# S7G2_footprint_with_caps_v1p0.net
KiCad netlist of a schematic drawn in EAGLE
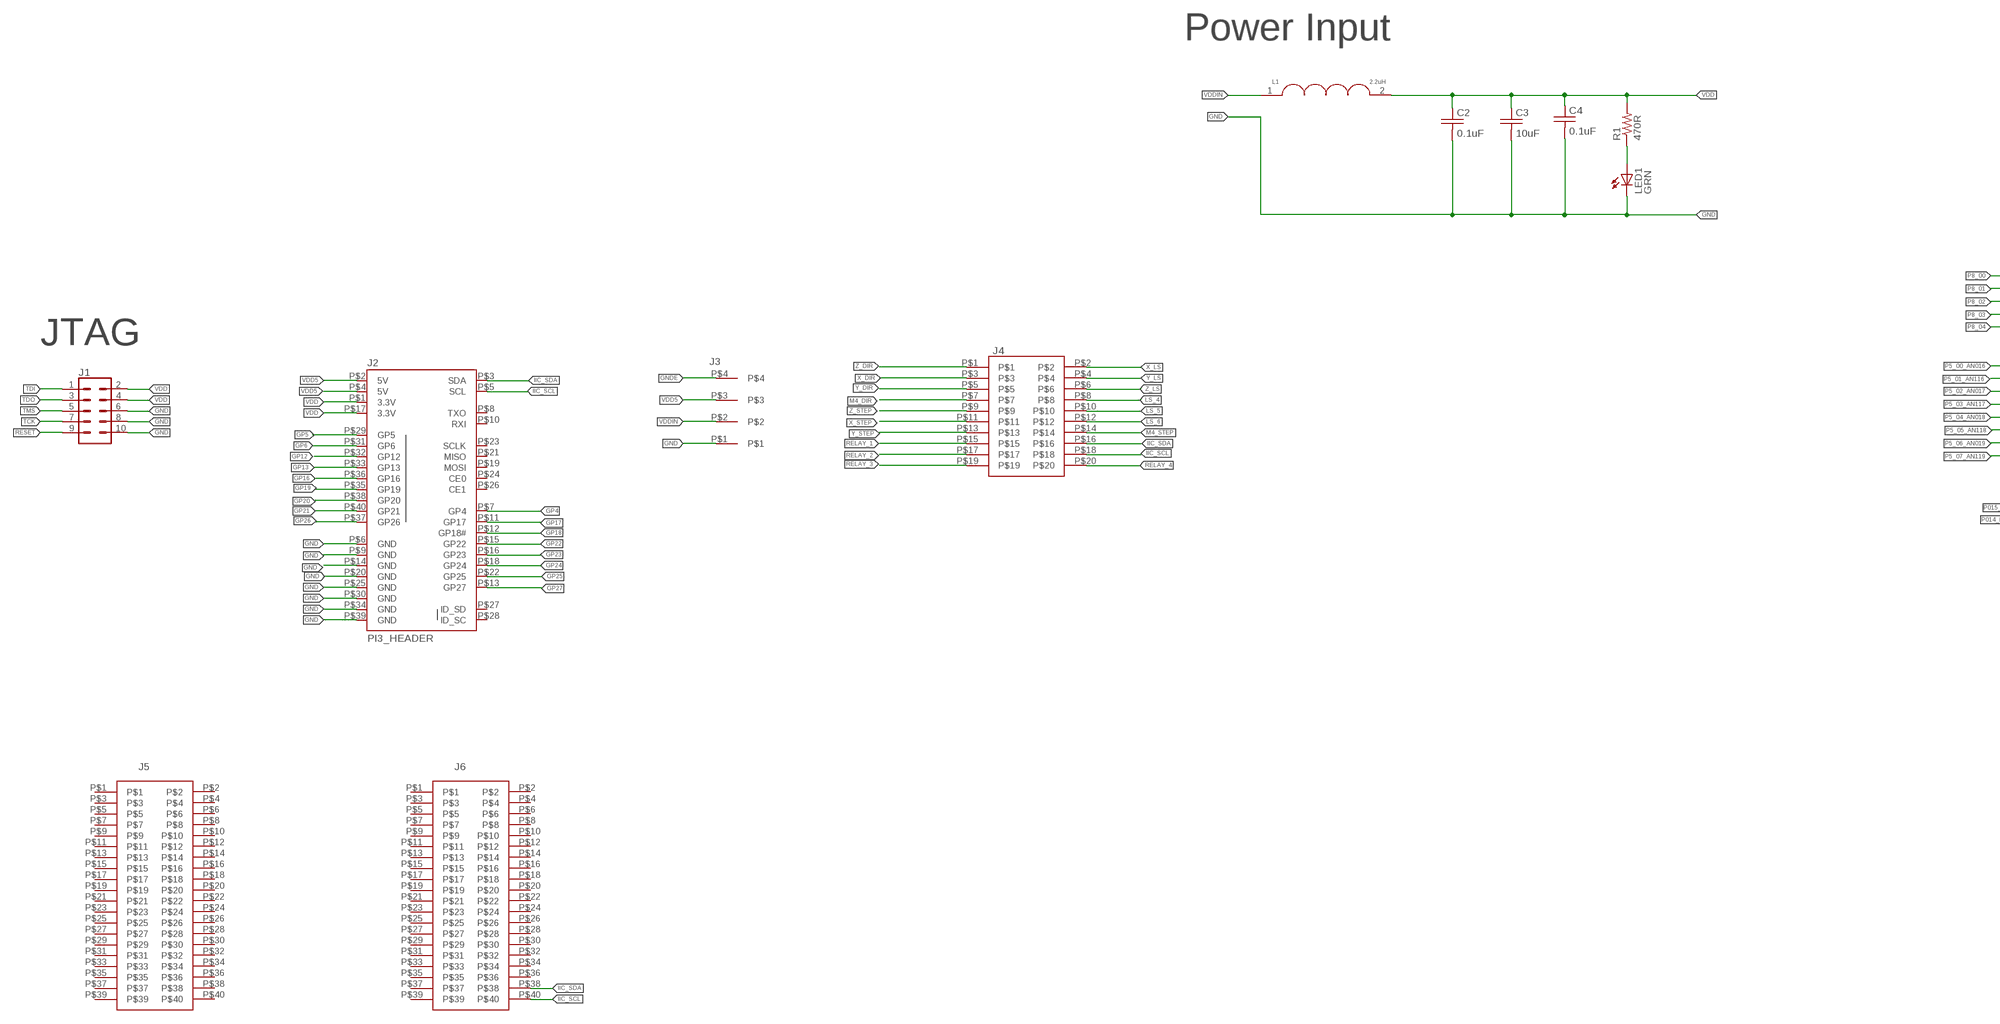
[diagram p0: schematic, sheet 1, part 1 of 3]
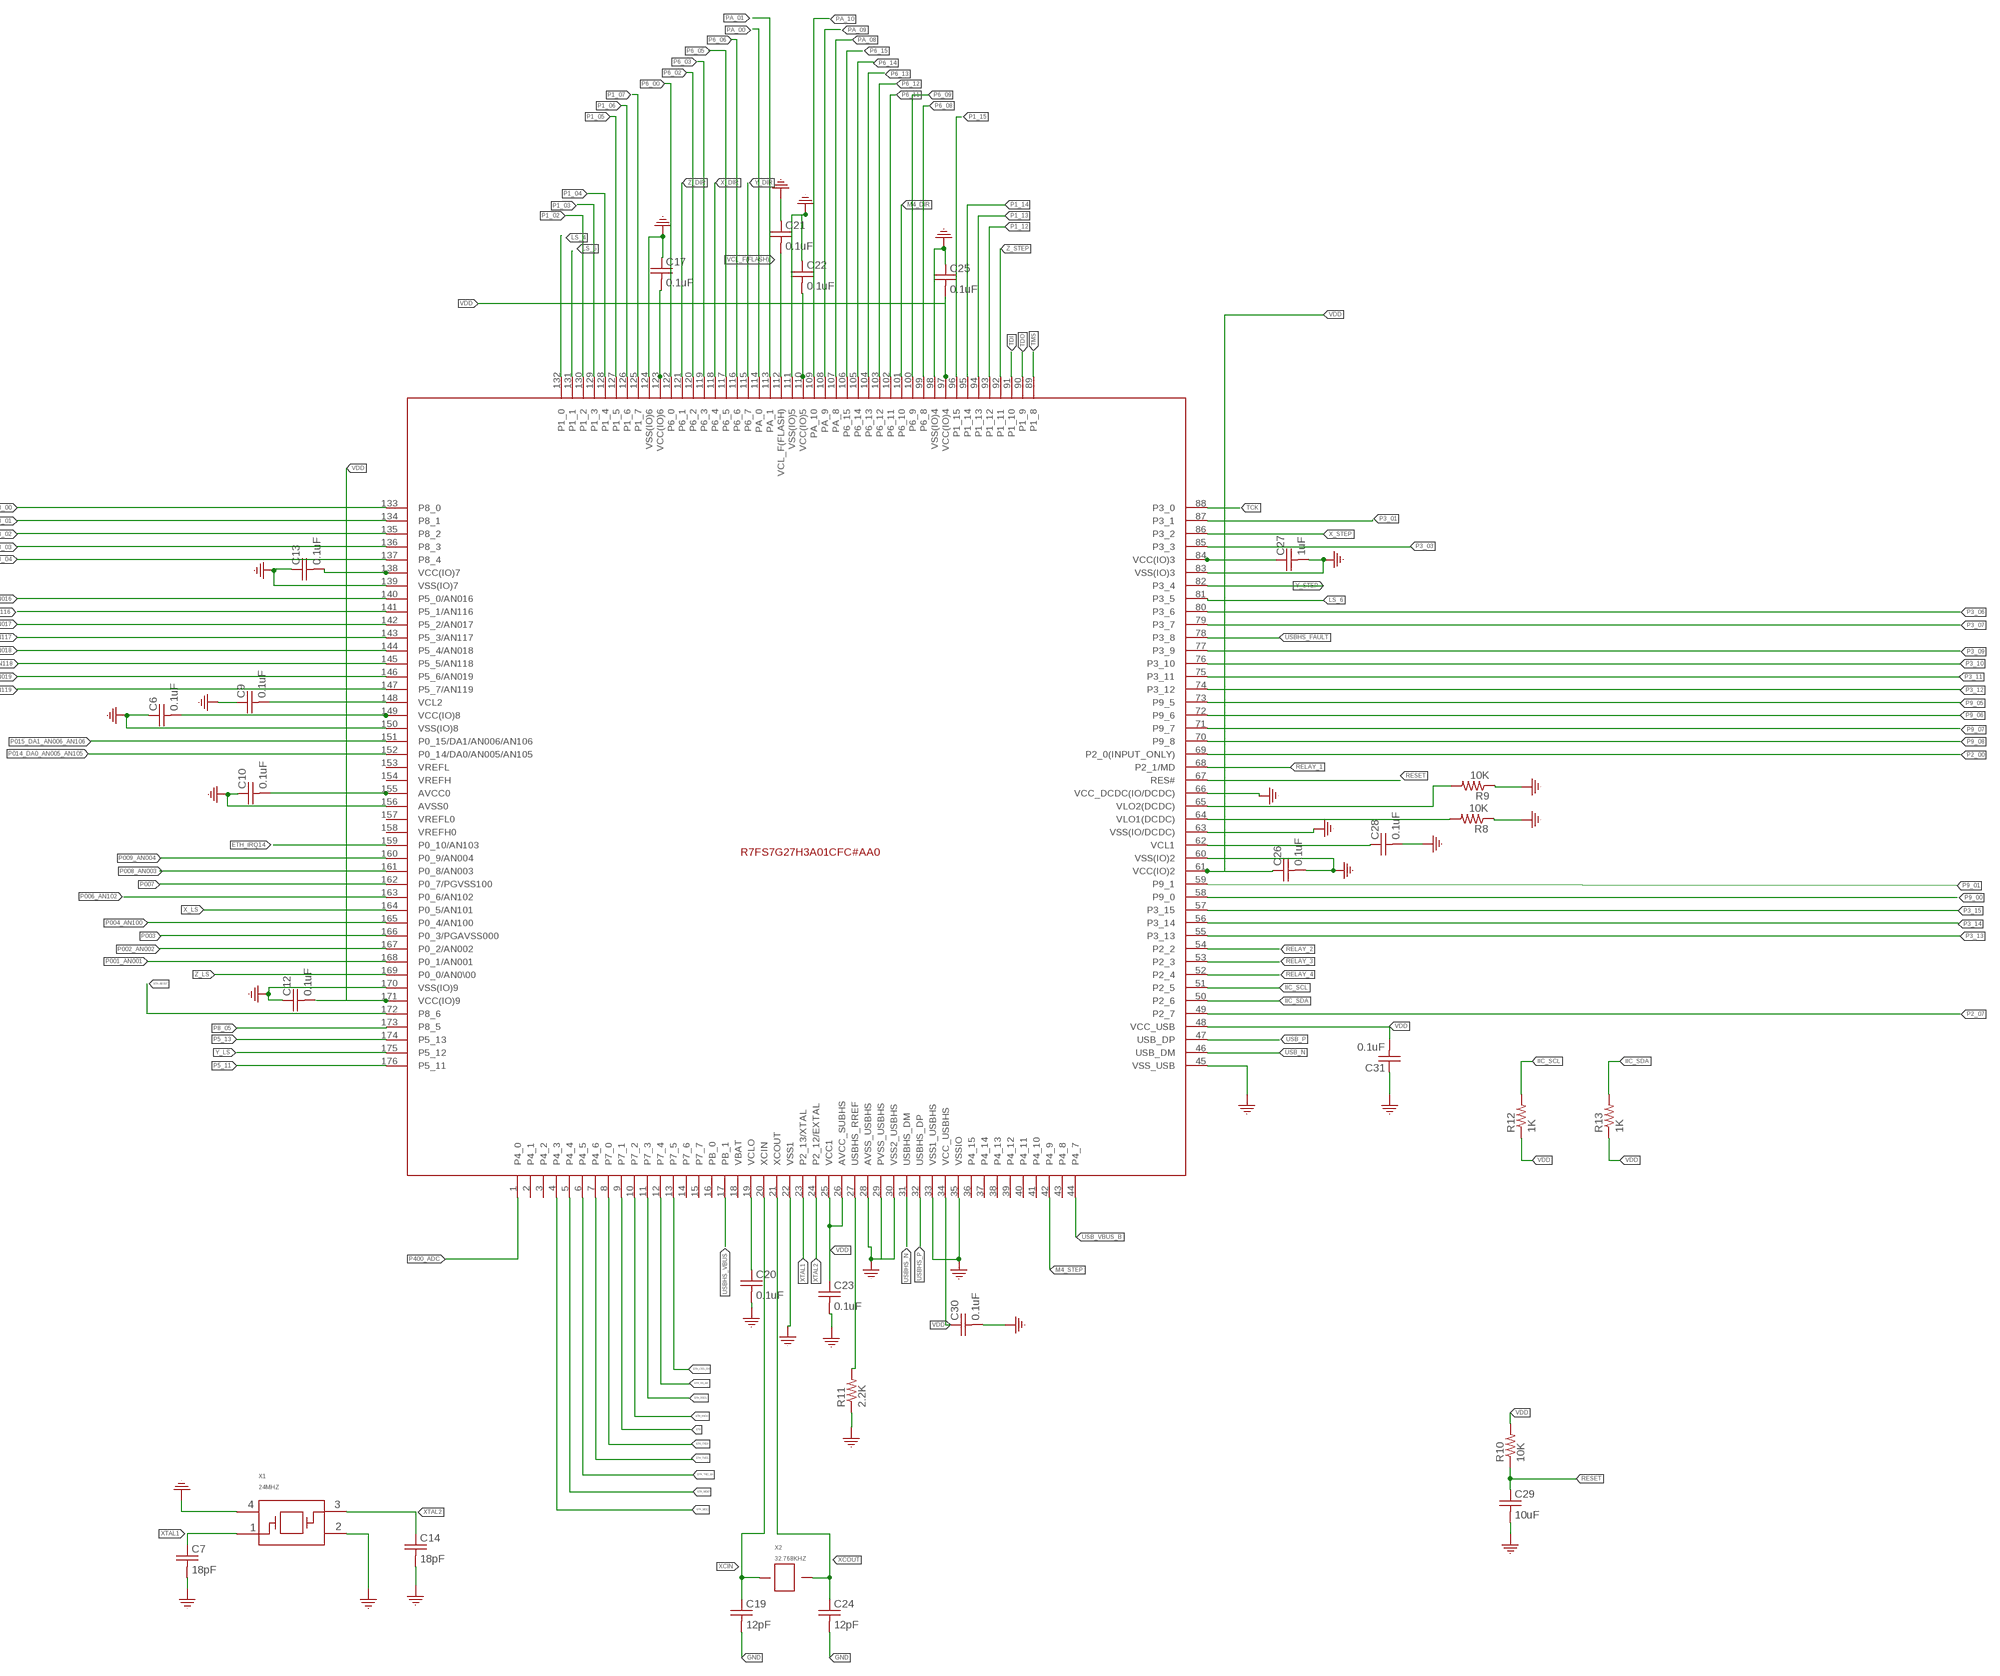
[diagram p1: schematic, sheet 1, part 2 of 3]
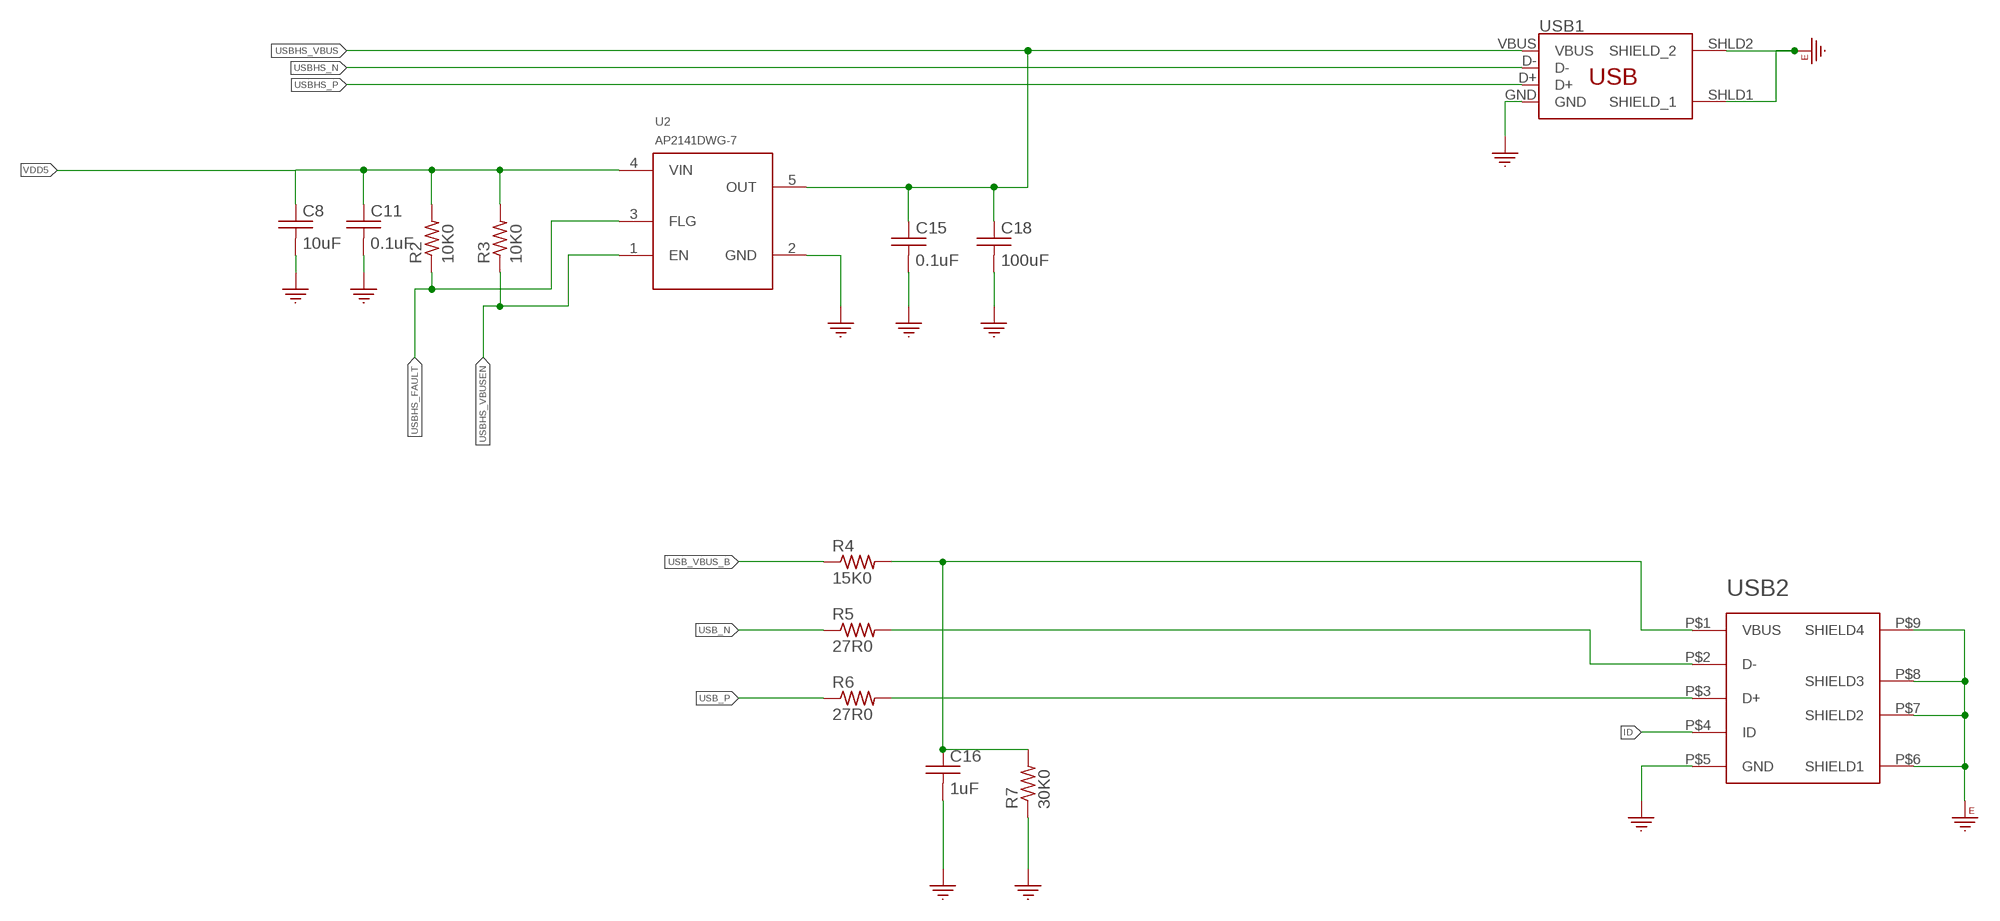
[diagram p2: schematic, sheet 1, part 3 of 3]

(export (version "E")
  (design (tool "Eeschema 10.0.6"))
  (components
    (comp (ref "C2")
      (value "0.1uF")
      (footprint "eagle-import:0402")
      (libsource (lib "eagle-import") (part "C_0402"))
    )
    (comp (ref "C3")
      (value "10uF")
      (footprint "eagle-import:0402")
      (libsource (lib "eagle-import") (part "C_0402"))
    )
    (comp (ref "C4")
      (value "0.1uF")
      (footprint "eagle-import:0402")
      (libsource (lib "eagle-import") (part "C_0402"))
    )
    (comp (ref "C6")
      (value "0.1uF")
      (footprint "eagle-import:0402")
      (libsource (lib "eagle-import") (part "C_0402"))
    )
    (comp (ref "C7")
      (value "18pF")
      (footprint "eagle-import:0402")
      (libsource (lib "eagle-import") (part "C_0402"))
    )
    (comp (ref "C8")
      (value "10uF")
      (footprint "eagle-import:0402")
      (libsource (lib "eagle-import") (part "C_0402"))
    )
    (comp (ref "C9")
      (value "0.1uF")
      (footprint "eagle-import:0402")
      (libsource (lib "eagle-import") (part "C_0402"))
    )
    (comp (ref "C10")
      (value "0.1uF")
      (footprint "eagle-import:0402")
      (libsource (lib "eagle-import") (part "C_0402"))
    )
    (comp (ref "C11")
      (value "0.1uF")
      (footprint "eagle-import:0402")
      (libsource (lib "eagle-import") (part "C_0402"))
    )
    (comp (ref "C12")
      (value "0.1uF")
      (footprint "eagle-import:0402")
      (libsource (lib "eagle-import") (part "C_0402"))
    )
    (comp (ref "C13")
      (value "0.1uF")
      (footprint "eagle-import:0402")
      (libsource (lib "eagle-import") (part "C_0402"))
    )
    (comp (ref "C14")
      (value "18pF")
      (footprint "eagle-import:0402")
      (libsource (lib "eagle-import") (part "C_0402"))
    )
    (comp (ref "C15")
      (value "0.1uF")
      (footprint "eagle-import:0402")
      (libsource (lib "eagle-import") (part "C_0402"))
    )
    (comp (ref "C16")
      (value "1uF")
      (footprint "eagle-import:0402")
      (libsource (lib "eagle-import") (part "C_0402"))
    )
    (comp (ref "C17")
      (value "0.1uF")
      (footprint "eagle-import:0402")
      (libsource (lib "eagle-import") (part "C_0402"))
    )
    (comp (ref "C18")
      (value "100uF")
      (footprint "eagle-import:C1210")
      (libsource (lib "eagle-import") (part "C_1210"))
    )
    (comp (ref "C19")
      (value "12pF")
      (footprint "eagle-import:0402")
      (libsource (lib "eagle-import") (part "C_0402"))
    )
    (comp (ref "C20")
      (value "0.1uF")
      (footprint "eagle-import:0402")
      (libsource (lib "eagle-import") (part "C_0402"))
    )
    (comp (ref "C21")
      (value "0.1uF")
      (footprint "eagle-import:0402")
      (libsource (lib "eagle-import") (part "C_0402"))
    )
    (comp (ref "C22")
      (value "0.1uF")
      (footprint "eagle-import:0402")
      (libsource (lib "eagle-import") (part "C_0402"))
    )
    (comp (ref "C23")
      (value "0.1uF")
      (footprint "eagle-import:0402")
      (libsource (lib "eagle-import") (part "C_0402"))
    )
    (comp (ref "C24")
      (value "12pF")
      (footprint "eagle-import:0402")
      (libsource (lib "eagle-import") (part "C_0402"))
    )
    (comp (ref "C25")
      (value "0.1uF")
      (footprint "eagle-import:0402")
      (libsource (lib "eagle-import") (part "C_0402"))
    )
    (comp (ref "C26")
      (value "0.1uF")
      (footprint "eagle-import:0402")
      (libsource (lib "eagle-import") (part "C_0402"))
    )
    (comp (ref "C27")
      (value "1uF")
      (footprint "eagle-import:0402")
      (libsource (lib "eagle-import") (part "C_0402"))
    )
    (comp (ref "C28")
      (value "0.1uF")
      (footprint "eagle-import:0402")
      (libsource (lib "eagle-import") (part "C_0402"))
    )
    (comp (ref "C29")
      (value "10uF")
      (footprint "eagle-import:0402")
      (libsource (lib "eagle-import") (part "C_0402"))
    )
    (comp (ref "C30")
      (value "0.1uF")
      (footprint "eagle-import:0402")
      (libsource (lib "eagle-import") (part "C_0402"))
    )
    (comp (ref "C31")
      (value "0.1uF")
      (footprint "eagle-import:0402")
      (libsource (lib "eagle-import") (part "C_0402"))
    )
    (comp (ref "J1")
      (value "CONN_05X2PTH")
      (footprint "eagle-import:2X5")
      (libsource (lib "eagle-import") (part "CONN_05X2PTH"))
    )
    (comp (ref "J2")
      (value "PI3_HEADER")
      (footprint "eagle-import:HEADER_2_X_20_.1_INCH")
      (libsource (lib "eagle-import") (part "PI3_HEADER"))
    )
    (comp (ref "J3")
      (value "3.81MM_1_X_4_RT_ANGLE_PLUG_HEADER")
      (footprint "eagle-import:1X4_3.81MM_PITCH")
      (libsource (lib "eagle-import") (part "3.81MM_1_X_4_RT_ANGLE_PLUG_HEADER"))
    )
    (comp (ref "J4")
      (value "2_X_10_HEADER_GENERIC")
      (footprint "eagle-import:2_X_10_.1_INCH")
      (libsource (lib "eagle-import") (part "2_X_10_HEADER_GENERIC"))
    )
    (comp (ref "J5")
      (value "HEADER_2_X_20_GENERIC")
      (footprint "eagle-import:HEADER_2_X_20_.1_INCH")
      (libsource (lib "eagle-import") (part "HEADER_2_X_20_GENERIC"))
    )
    (comp (ref "J6")
      (value "HEADER_2_X_20_GENERIC")
      (footprint "eagle-import:HEADER_2_X_20_.1_INCH")
      (libsource (lib "eagle-import") (part "HEADER_2_X_20_GENERIC"))
    )
    (comp (ref "L1")
      (value "2.2uH")
      (footprint "eagle-import:1008_(2520_METRIC)")
      (libsource (lib "eagle-import") (part "INDUCTOR_1008_2.2_MH_1.3A"))
    )
    (comp (ref "LED1")
      (value "LED_0805_GREEN")
      (footprint "eagle-import:LED_0805_GREEN")
      (libsource (lib "eagle-import") (part "LED_0805_GREEN"))
    )
    (comp (ref "R1")
      (value "470R")
      (footprint "eagle-import:0402")
      (libsource (lib "eagle-import") (part "R_0402"))
    )
    (comp (ref "R2")
      (value "10K0")
      (footprint "eagle-import:0402")
      (libsource (lib "eagle-import") (part "R_0402"))
    )
    (comp (ref "R3")
      (value "10K0")
      (footprint "eagle-import:0402")
      (libsource (lib "eagle-import") (part "R_0402"))
    )
    (comp (ref "R4")
      (value "15K0")
      (footprint "eagle-import:0402")
      (libsource (lib "eagle-import") (part "R_0402"))
    )
    (comp (ref "R5")
      (value "27R0")
      (footprint "eagle-import:0402")
      (libsource (lib "eagle-import") (part "R_0402"))
    )
    (comp (ref "R6")
      (value "27R0")
      (footprint "eagle-import:0402")
      (libsource (lib "eagle-import") (part "R_0402"))
    )
    (comp (ref "R7")
      (value "30K0")
      (footprint "eagle-import:0402")
      (libsource (lib "eagle-import") (part "R_0402"))
    )
    (comp (ref "R8")
      (value "10K")
      (footprint "eagle-import:0402")
      (libsource (lib "eagle-import") (part "R_0402"))
    )
    (comp (ref "R9")
      (value "10K")
      (footprint "eagle-import:0402")
      (libsource (lib "eagle-import") (part "R_0402"))
    )
    (comp (ref "R10")
      (value "10K")
      (footprint "eagle-import:0402")
      (libsource (lib "eagle-import") (part "R_0402"))
    )
    (comp (ref "R11")
      (value "2.2K")
      (footprint "eagle-import:0402")
      (libsource (lib "eagle-import") (part "R_0402"))
    )
    (comp (ref "R12")
      (value "1K")
      (footprint "eagle-import:0402")
      (libsource (lib "eagle-import") (part "R_0402"))
    )
    (comp (ref "R13")
      (value "1K")
      (footprint "eagle-import:0402")
      (libsource (lib "eagle-import") (part "R_0402"))
    )
    (comp (ref "U2")
      (value "AP2141DWG-5")
      (footprint "eagle-import:SOT-23-5")
      (libsource (lib "eagle-import") (part "AP2141DWG-5"))
    )
    (comp (ref "U5")
      (value "S7G2_X_176")
      (footprint "eagle-import:LQFP176_24X24")
      (libsource (lib "eagle-import") (part "S7G2_X_176"))
    )
    (comp (ref "USB1")
      (value "USB_A")
      (footprint "eagle-import:USB_A_SMT")
      (libsource (lib "eagle-import") (part "USB_A"))
    )
    (comp (ref "USB2")
      (value "USB_MICRO-B")
      (footprint "eagle-import:USB_MICRO-B")
      (libsource (lib "eagle-import") (part "USB_MICRO-B"))
    )
    (comp (ref "X1")
      (value "24MHZ")
      (footprint "eagle-import:SMD_3225")
      (libsource (lib "eagle-import") (part "XTAL_24_MHZ"))
    )
    (comp (ref "X2")
      (value "32.768KHZ")
      (footprint "eagle-import:SMD_X_2_PADS")
      (libsource (lib "eagle-import") (part "XTAL_32.768KHZ"))
    )
  )
  (nets
    (net (code "1") (name "ETH") (class "Default")
      (node (ref "U5") (pin "9") (pinfunction "P7_1_9") (pintype "bidirectional"))
    )
    (net (code "2") (name "ETH_CRS_DV") (class "Default")
      (node (ref "U5") (pin "13") (pinfunction "P7_5_13") (pintype "bidirectional"))
    )
    (net (code "3") (name "ETH_IRQ14") (class "Default")
      (node (ref "U5") (pin "159") (pinfunction "P0_10/AN103_159") (pintype "bidirectional"))
    )
    (net (code "4") (name "ETH_MDC") (class "Default")
      (node (ref "U5") (pin "4") (pinfunction "P4_3_4") (pintype "bidirectional"))
    )
    (net (code "5") (name "ETH_MDIO") (class "Default")
      (node (ref "U5") (pin "5") (pinfunction "P4_4_5") (pintype "bidirectional"))
    )
    (net (code "6") (name "ETH_RESET") (class "Default")
      (node (ref "U5") (pin "172") (pinfunction "P8_6_172") (pintype "bidirectional"))
    )
    (net (code "7") (name "ETH_RXD0") (class "Default")
      (node (ref "U5") (pin "10") (pinfunction "P7_2_10") (pintype "bidirectional"))
    )
    (net (code "8") (name "ETH_RXD1") (class "Default")
      (node (ref "U5") (pin "11") (pinfunction "P7_3_11") (pintype "bidirectional"))
    )
    (net (code "9") (name "ETH_RX_ER") (class "Default")
      (node (ref "U5") (pin "12") (pinfunction "P7_4_12") (pintype "bidirectional"))
    )
    (net (code "10") (name "ETH_TXD0") (class "Default")
      (node (ref "U5") (pin "8") (pinfunction "P7_0_8") (pintype "bidirectional"))
    )
    (net (code "11") (name "ETH_TXD1") (class "Default")
      (node (ref "U5") (pin "7") (pinfunction "P4_6_7") (pintype "bidirectional"))
    )
    (net (code "12") (name "ETH_TXD_EN") (class "Default")
      (node (ref "U5") (pin "6") (pinfunction "P4_5_6") (pintype "bidirectional"))
    )
    (net (code "13") (name "GND") (class "Default")
      (node (ref "C10") (pin "P$1") (pinfunction "1_P$1") (pintype "passive"))
      (node (ref "C11") (pin "P$2") (pinfunction "2_P$2") (pintype "passive"))
      (node (ref "C12") (pin "P$1") (pinfunction "1_P$1") (pintype "passive"))
      (node (ref "C13") (pin "P$1") (pinfunction "1_P$1") (pintype "passive"))
      (node (ref "C14") (pin "P$2") (pinfunction "2_P$2") (pintype "passive"))
      (node (ref "C15") (pin "P$2") (pinfunction "2_P$2") (pintype "passive"))
      (node (ref "C16") (pin "P$2") (pinfunction "2_P$2") (pintype "passive"))
      (node (ref "C17") (pin "P$1") (pinfunction "1_P$1") (pintype "passive"))
      (node (ref "C18") (pin "2") (pinfunction "2_2") (pintype "passive"))
      (node (ref "C19") (pin "P$2") (pinfunction "2_P$2") (pintype "passive"))
      (node (ref "C2") (pin "P$2") (pinfunction "2_P$2") (pintype "passive"))
      (node (ref "C20") (pin "P$2") (pinfunction "2_P$2") (pintype "passive"))
      (node (ref "C21") (pin "P$1") (pinfunction "1_P$1") (pintype "passive"))
      (node (ref "C22") (pin "P$1") (pinfunction "1_P$1") (pintype "passive"))
      (node (ref "C23") (pin "P$2") (pinfunction "2_P$2") (pintype "passive"))
      (node (ref "C24") (pin "P$2") (pinfunction "2_P$2") (pintype "passive"))
      (node (ref "C25") (pin "P$1") (pinfunction "1_P$1") (pintype "passive"))
      (node (ref "C26") (pin "P$2") (pinfunction "2_P$2") (pintype "passive"))
      (node (ref "C27") (pin "P$2") (pinfunction "2_P$2") (pintype "passive"))
      (node (ref "C28") (pin "P$2") (pinfunction "2_P$2") (pintype "passive"))
      (node (ref "C29") (pin "P$2") (pinfunction "2_P$2") (pintype "passive"))
      (node (ref "C3") (pin "P$2") (pinfunction "2_P$2") (pintype "passive"))
      (node (ref "C30") (pin "P$2") (pinfunction "2_P$2") (pintype "passive"))
      (node (ref "C31") (pin "P$1") (pinfunction "1_P$1") (pintype "passive"))
      (node (ref "C4") (pin "P$2") (pinfunction "2_P$2") (pintype "passive"))
      (node (ref "C6") (pin "P$1") (pinfunction "1_P$1") (pintype "passive"))
      (node (ref "C7") (pin "P$2") (pinfunction "2_P$2") (pintype "passive"))
      (node (ref "C8") (pin "P$2") (pinfunction "2_P$2") (pintype "passive"))
      (node (ref "C9") (pin "P$1") (pinfunction "1_P$1") (pintype "passive"))
      (node (ref "J1") (pin "10") (pinfunction "10_10") (pintype "passive"))
      (node (ref "J1") (pin "6") (pinfunction "6_6") (pintype "passive"))
      (node (ref "J1") (pin "8") (pinfunction "8_8") (pintype "passive"))
      (node (ref "J2") (pin "P$14") (pinfunction "GND_P$14") (pintype "power_in"))
      (node (ref "J2") (pin "P$20") (pinfunction "GND_P$20") (pintype "power_in"))
      (node (ref "J2") (pin "P$25") (pinfunction "GND_P$25") (pintype "power_in"))
      (node (ref "J2") (pin "P$30") (pinfunction "GND_P$30") (pintype "power_in"))
      (node (ref "J2") (pin "P$34") (pinfunction "GND_P$34") (pintype "power_in"))
      (node (ref "J2") (pin "P$39") (pinfunction "GND_P$39") (pintype "power_in"))
      (node (ref "J2") (pin "P$6") (pinfunction "GND_P$6") (pintype "power_in"))
      (node (ref "J2") (pin "P$9") (pinfunction "GND_P$9") (pintype "power_in"))
      (node (ref "J3") (pin "P$1") (pinfunction "P$1_P$1") (pintype "bidirectional"))
      (node (ref "LED1") (pin "C") (pinfunction "C_C") (pintype "passive"))
      (node (ref "R11") (pin "P$1") (pinfunction "1_P$1") (pintype "passive"))
      (node (ref "R7") (pin "P$1") (pinfunction "1_P$1") (pintype "passive"))
      (node (ref "R8") (pin "P$1") (pinfunction "1_P$1") (pintype "passive"))
      (node (ref "R9") (pin "P$1") (pinfunction "1_P$1") (pintype "passive"))
      (node (ref "U2") (pin "2") (pinfunction "GND_2") (pintype "input"))
      (node (ref "U5") (pin "111") (pinfunction "VSS(IO)5_111") (pintype "bidirectional"))
      (node (ref "U5") (pin "124") (pinfunction "VSS(IO)6_124") (pintype "bidirectional"))
      (node (ref "U5") (pin "139") (pinfunction "VSS(IO)7_139") (pintype "bidirectional"))
      (node (ref "U5") (pin "150") (pinfunction "VSS(IO)8_150") (pintype "bidirectional"))
      (node (ref "U5") (pin "156") (pinfunction "AVSS0_156") (pintype "bidirectional"))
      (node (ref "U5") (pin "170") (pinfunction "VSS(IO)9_170") (pintype "bidirectional"))
      (node (ref "U5") (pin "22") (pinfunction "VSS1_22") (pintype "bidirectional"))
      (node (ref "U5") (pin "28") (pinfunction "AVSS_USBHS_28") (pintype "bidirectional"))
      (node (ref "U5") (pin "29") (pinfunction "PVSS_USBHS_29") (pintype "bidirectional"))
      (node (ref "U5") (pin "30") (pinfunction "VSS2_USBHS_30") (pintype "bidirectional"))
      (node (ref "U5") (pin "33") (pinfunction "VSS1_USBHS_33") (pintype "bidirectional"))
      (node (ref "U5") (pin "35") (pinfunction "VSSIO_35") (pintype "bidirectional"))
      (node (ref "U5") (pin "45") (pinfunction "VSS_USB_45") (pintype "bidirectional"))
      (node (ref "U5") (pin "60") (pinfunction "VSS(IO)2_60") (pintype "bidirectional"))
      (node (ref "U5") (pin "63") (pinfunction "VSS(IO/DCDC)_63") (pintype "bidirectional"))
      (node (ref "U5") (pin "66") (pinfunction "VCC_DCDC(IO/DCDC)_66") (pintype "bidirectional"))
      (node (ref "U5") (pin "83") (pinfunction "VSS(IO)3_83") (pintype "bidirectional"))
      (node (ref "U5") (pin "98") (pinfunction "VSS(IO)4_98") (pintype "bidirectional"))
      (node (ref "USB1") (pin "GND") (pinfunction "GND_GND") (pintype "power_in"))
      (node (ref "USB2") (pin "P$5") (pinfunction "GND_P$5") (pintype "bidirectional"))
      (node (ref "X1") (pin "2") (pinfunction "2_2") (pintype "bidirectional"))
      (node (ref "X1") (pin "4") (pinfunction "4_4") (pintype "bidirectional"))
    )
    (net (code "14") (name "GNDE") (class "Default")
      (node (ref "J3") (pin "P$4") (pinfunction "P$4_P$4") (pintype "bidirectional"))
      (node (ref "USB1") (pin "SHLD1") (pinfunction "SHIELD_1_SHLD1") (pintype "bidirectional"))
      (node (ref "USB1") (pin "SHLD2") (pinfunction "SHIELD_2_SHLD2") (pintype "bidirectional"))
      (node (ref "USB2") (pin "P$6") (pinfunction "SHIELD1_P$6") (pintype "bidirectional"))
      (node (ref "USB2") (pin "P$7") (pinfunction "SHIELD2_P$7") (pintype "bidirectional"))
      (node (ref "USB2") (pin "P$8") (pinfunction "SHIELD3_P$8") (pintype "bidirectional"))
      (node (ref "USB2") (pin "P$9") (pinfunction "SHIELD4_P$9") (pintype "bidirectional"))
    )
    (net (code "15") (name "GP4") (class "Default")
      (node (ref "J2") (pin "P$7") (pinfunction "GP4_P$7") (pintype "bidirectional"))
    )
    (net (code "16") (name "GP5") (class "Default")
      (node (ref "J2") (pin "P$29") (pinfunction "GP5_P$29") (pintype "bidirectional"))
    )
    (net (code "17") (name "GP6") (class "Default")
      (node (ref "J2") (pin "P$31") (pinfunction "GP6_P$31") (pintype "bidirectional"))
    )
    (net (code "18") (name "GP12") (class "Default")
      (node (ref "J2") (pin "P$32") (pinfunction "GP12_P$32") (pintype "bidirectional"))
    )
    (net (code "19") (name "GP13") (class "Default")
      (node (ref "J2") (pin "P$33") (pinfunction "GP13_P$33") (pintype "bidirectional"))
    )
    (net (code "20") (name "GP16") (class "Default")
      (node (ref "J2") (pin "P$36") (pinfunction "GP16_P$36") (pintype "bidirectional"))
    )
    (net (code "21") (name "GP17") (class "Default")
      (node (ref "J2") (pin "P$11") (pinfunction "GP17_P$11") (pintype "bidirectional"))
    )
    (net (code "22") (name "GP18") (class "Default")
      (node (ref "J2") (pin "P$12") (pinfunction "GP18#_P$12") (pintype "bidirectional"))
    )
    (net (code "23") (name "GP19") (class "Default")
      (node (ref "J2") (pin "P$35") (pinfunction "GP19_P$35") (pintype "bidirectional"))
    )
    (net (code "24") (name "GP20") (class "Default")
      (node (ref "J2") (pin "P$38") (pinfunction "GP20_P$38") (pintype "bidirectional"))
    )
    (net (code "25") (name "GP21") (class "Default")
      (node (ref "J2") (pin "P$40") (pinfunction "GP21_P$40") (pintype "bidirectional"))
    )
    (net (code "26") (name "GP22") (class "Default")
      (node (ref "J2") (pin "P$15") (pinfunction "GP22_P$15") (pintype "bidirectional"))
    )
    (net (code "27") (name "GP23") (class "Default")
      (node (ref "J2") (pin "P$16") (pinfunction "GP23_P$16") (pintype "bidirectional"))
    )
    (net (code "28") (name "GP24") (class "Default")
      (node (ref "J2") (pin "P$18") (pinfunction "GP24_P$18") (pintype "bidirectional"))
    )
    (net (code "29") (name "GP25") (class "Default")
      (node (ref "J2") (pin "P$22") (pinfunction "GP25_P$22") (pintype "bidirectional"))
    )
    (net (code "30") (name "GP26") (class "Default")
      (node (ref "J2") (pin "P$37") (pinfunction "GP26_P$37") (pintype "bidirectional"))
    )
    (net (code "31") (name "GP27") (class "Default")
      (node (ref "J2") (pin "P$13") (pinfunction "GP27_P$13") (pintype "bidirectional"))
    )
    (net (code "32") (name "ID") (class "Default")
      (node (ref "USB2") (pin "P$4") (pinfunction "ID_P$4") (pintype "bidirectional"))
    )
    (net (code "33") (name "IIC_SCL") (class "Default")
      (node (ref "J2") (pin "P$5") (pinfunction "SCL_P$5") (pintype "bidirectional"))
      (node (ref "J4") (pin "P$18") (pinfunction "P$18_P$18") (pintype "bidirectional"))
      (node (ref "J6") (pin "P$40") (pinfunction "P$40_P$40") (pintype "bidirectional"))
      (node (ref "R12") (pin "P$2") (pinfunction "2_P$2") (pintype "passive"))
      (node (ref "U5") (pin "51") (pinfunction "P2_5_51") (pintype "bidirectional"))
    )
    (net (code "34") (name "IIC_SDA") (class "Default")
      (node (ref "J2") (pin "P$3") (pinfunction "SDA_P$3") (pintype "bidirectional"))
      (node (ref "J4") (pin "P$16") (pinfunction "P$16_P$16") (pintype "bidirectional"))
      (node (ref "J6") (pin "P$38") (pinfunction "P$38_P$38") (pintype "bidirectional"))
      (node (ref "R13") (pin "P$2") (pinfunction "2_P$2") (pintype "passive"))
      (node (ref "U5") (pin "50") (pinfunction "P2_6_50") (pintype "bidirectional"))
    )
    (net (code "35") (name "LS_4") (class "Default")
      (node (ref "J4") (pin "P$8") (pinfunction "P$8_P$8") (pintype "bidirectional"))
      (node (ref "U5") (pin "132") (pinfunction "P1_0_132") (pintype "bidirectional"))
    )
    (net (code "36") (name "LS_5") (class "Default")
      (node (ref "J4") (pin "P$10") (pinfunction "P$10_P$10") (pintype "bidirectional"))
      (node (ref "U5") (pin "131") (pinfunction "P1_1_131") (pintype "bidirectional"))
    )
    (net (code "37") (name "LS_6") (class "Default")
      (node (ref "J4") (pin "P$12") (pinfunction "P$12_P$12") (pintype "bidirectional"))
      (node (ref "U5") (pin "81") (pinfunction "P3_5_81") (pintype "bidirectional"))
    )
    (net (code "38") (name "M4_DIR") (class "Default")
      (node (ref "J4") (pin "P$7") (pinfunction "P$7_P$7") (pintype "bidirectional"))
      (node (ref "U5") (pin "101") (pinfunction "P6_10_101") (pintype "bidirectional"))
    )
    (net (code "39") (name "M4_STEP") (class "Default")
      (node (ref "J4") (pin "P$14") (pinfunction "P$14_P$14") (pintype "bidirectional"))
      (node (ref "U5") (pin "42") (pinfunction "P4_9_42") (pintype "bidirectional"))
    )
    (net (code "40") (name "Net-(C9-2)") (class "Default")
      (node (ref "C9") (pin "P$2") (pinfunction "2_P$2") (pintype "passive"))
      (node (ref "U5") (pin "148") (pinfunction "VCL2_148") (pintype "bidirectional"))
    )
    (net (code "41") (name "Net-(C16-1)") (class "Default")
      (node (ref "C16") (pin "P$1") (pinfunction "1_P$1") (pintype "passive"))
      (node (ref "R4") (pin "P$2") (pinfunction "2_P$2") (pintype "passive"))
      (node (ref "R7") (pin "P$2") (pinfunction "2_P$2") (pintype "passive"))
      (node (ref "USB2") (pin "P$1") (pinfunction "VBUS_P$1") (pintype "bidirectional"))
    )
    (net (code "42") (name "Net-(C20-1)") (class "Default")
      (node (ref "C20") (pin "P$1") (pinfunction "1_P$1") (pintype "passive"))
      (node (ref "U5") (pin "19") (pinfunction "VCLO_19") (pintype "bidirectional"))
    )
    (net (code "43") (name "Net-(C28-1)") (class "Default")
      (node (ref "C28") (pin "P$1") (pinfunction "1_P$1") (pintype "passive"))
      (node (ref "U5") (pin "62") (pinfunction "VCL1_62") (pintype "bidirectional"))
    )
    (net (code "44") (name "Net-(R1-1)") (class "Default")
      (node (ref "LED1") (pin "A") (pinfunction "A_A") (pintype "passive"))
      (node (ref "R1") (pin "P$1") (pinfunction "1_P$1") (pintype "passive"))
    )
    (net (code "45") (name "Net-(R5-2)") (class "Default")
      (node (ref "R5") (pin "P$2") (pinfunction "2_P$2") (pintype "passive"))
      (node (ref "USB2") (pin "P$2") (pinfunction "D-_P$2") (pintype "bidirectional"))
    )
    (net (code "46") (name "Net-(R6-2)") (class "Default")
      (node (ref "R6") (pin "P$2") (pinfunction "2_P$2") (pintype "passive"))
      (node (ref "USB2") (pin "P$3") (pinfunction "D+_P$3") (pintype "bidirectional"))
    )
    (net (code "47") (name "Net-(R8-2)") (class "Default")
      (node (ref "R8") (pin "P$2") (pinfunction "2_P$2") (pintype "passive"))
      (node (ref "U5") (pin "64") (pinfunction "VLO1(DCDC)_64") (pintype "bidirectional"))
    )
    (net (code "48") (name "Net-(R9-2)") (class "Default")
      (node (ref "R9") (pin "P$2") (pinfunction "2_P$2") (pintype "passive"))
      (node (ref "U5") (pin "65") (pinfunction "VLO2(DCDC)_65") (pintype "bidirectional"))
    )
    (net (code "49") (name "Net-(R11-2)") (class "Default")
      (node (ref "R11") (pin "P$2") (pinfunction "2_P$2") (pintype "passive"))
      (node (ref "U5") (pin "27") (pinfunction "USBHS_RREF_27") (pintype "bidirectional"))
    )
    (net (code "50") (name "P1_02") (class "Default")
      (node (ref "U5") (pin "130") (pinfunction "P1_2_130") (pintype "bidirectional"))
    )
    (net (code "51") (name "P1_03") (class "Default")
      (node (ref "U5") (pin "129") (pinfunction "P1_3_129") (pintype "bidirectional"))
    )
    (net (code "52") (name "P1_04") (class "Default")
      (node (ref "U5") (pin "128") (pinfunction "P1_4_128") (pintype "bidirectional"))
    )
    (net (code "53") (name "P1_05") (class "Default")
      (node (ref "U5") (pin "127") (pinfunction "P1_5_127") (pintype "bidirectional"))
    )
    (net (code "54") (name "P1_06") (class "Default")
      (node (ref "U5") (pin "126") (pinfunction "P1_6_126") (pintype "bidirectional"))
    )
    (net (code "55") (name "P1_07") (class "Default")
      (node (ref "U5") (pin "125") (pinfunction "P1_7_125") (pintype "bidirectional"))
    )
    (net (code "56") (name "P1_12") (class "Default")
      (node (ref "U5") (pin "93") (pinfunction "P1_12_93") (pintype "bidirectional"))
    )
    (net (code "57") (name "P1_13") (class "Default")
      (node (ref "U5") (pin "94") (pinfunction "P1_13_94") (pintype "bidirectional"))
    )
    (net (code "58") (name "P1_14") (class "Default")
      (node (ref "U5") (pin "95") (pinfunction "P1_14_95") (pintype "bidirectional"))
    )
    (net (code "59") (name "P1_15") (class "Default")
      (node (ref "U5") (pin "96") (pinfunction "P1_15_96") (pintype "bidirectional"))
    )
    (net (code "60") (name "P001_AN001") (class "Default")
      (node (ref "U5") (pin "168") (pinfunction "P0_1/AN001_168") (pintype "bidirectional"))
    )
    (net (code "61") (name "P2_00") (class "Default")
      (node (ref "U5") (pin "69") (pinfunction "P2_0(INPUT_ONLY)_69") (pintype "bidirectional"))
    )
    (net (code "62") (name "P2_07") (class "Default")
      (node (ref "U5") (pin "49") (pinfunction "P2_7_49") (pintype "bidirectional"))
    )
    (net (code "63") (name "P002_AN002") (class "Default")
      (node (ref "U5") (pin "167") (pinfunction "P0_2/AN002_167") (pintype "bidirectional"))
    )
    (net (code "64") (name "P003") (class "Default")
      (node (ref "U5") (pin "166") (pinfunction "P0_3/PGAVSS000_166") (pintype "bidirectional"))
    )
    (net (code "65") (name "P3_01") (class "Default")
      (node (ref "U5") (pin "87") (pinfunction "P3_1_87") (pintype "bidirectional"))
    )
    (net (code "66") (name "P3_03") (class "Default")
      (node (ref "U5") (pin "85") (pinfunction "P3_3_85") (pintype "bidirectional"))
    )
    (net (code "67") (name "P3_06") (class "Default")
      (node (ref "U5") (pin "80") (pinfunction "P3_6_80") (pintype "bidirectional"))
    )
    (net (code "68") (name "P3_07") (class "Default")
      (node (ref "U5") (pin "79") (pinfunction "P3_7_79") (pintype "bidirectional"))
    )
    (net (code "69") (name "P3_09") (class "Default")
      (node (ref "U5") (pin "77") (pinfunction "P3_9_77") (pintype "bidirectional"))
    )
    (net (code "70") (name "P3_10") (class "Default")
      (node (ref "U5") (pin "76") (pinfunction "P3_10_76") (pintype "bidirectional"))
    )
    (net (code "71") (name "P3_11") (class "Default")
      (node (ref "U5") (pin "75") (pinfunction "P3_11_75") (pintype "bidirectional"))
    )
    (net (code "72") (name "P3_12") (class "Default")
      (node (ref "U5") (pin "74") (pinfunction "P3_12_74") (pintype "bidirectional"))
    )
    (net (code "73") (name "P3_13") (class "Default")
      (node (ref "U5") (pin "55") (pinfunction "P3_13_55") (pintype "bidirectional"))
    )
    (net (code "74") (name "P3_14") (class "Default")
      (node (ref "U5") (pin "56") (pinfunction "P3_14_56") (pintype "bidirectional"))
    )
    (net (code "75") (name "P3_15") (class "Default")
      (node (ref "U5") (pin "57") (pinfunction "P3_15_57") (pintype "bidirectional"))
    )
    (net (code "76") (name "P004_AN100") (class "Default")
      (node (ref "U5") (pin "165") (pinfunction "P0_4/AN100_165") (pintype "bidirectional"))
    )
    (net (code "77") (name "P5_00_AN016") (class "Default")
      (node (ref "U5") (pin "140") (pinfunction "P5_0/AN016_140") (pintype "bidirectional"))
    )
    (net (code "78") (name "P5_01_AN116") (class "Default")
      (node (ref "U5") (pin "141") (pinfunction "P5_1/AN116_141") (pintype "bidirectional"))
    )
    (net (code "79") (name "P5_02_AN017") (class "Default")
      (node (ref "U5") (pin "142") (pinfunction "P5_2/AN017_142") (pintype "bidirectional"))
    )
    (net (code "80") (name "P5_03_AN117") (class "Default")
      (node (ref "U5") (pin "143") (pinfunction "P5_3/AN117_143") (pintype "bidirectional"))
    )
    (net (code "81") (name "P5_04_AN018") (class "Default")
      (node (ref "U5") (pin "144") (pinfunction "P5_4/AN018_144") (pintype "bidirectional"))
    )
    (net (code "82") (name "P5_05_AN118") (class "Default")
      (node (ref "U5") (pin "145") (pinfunction "P5_5/AN118_145") (pintype "bidirectional"))
    )
    (net (code "83") (name "P5_06_AN019") (class "Default")
      (node (ref "U5") (pin "146") (pinfunction "P5_6/AN019_146") (pintype "bidirectional"))
    )
    (net (code "84") (name "P5_07_AN119") (class "Default")
      (node (ref "U5") (pin "147") (pinfunction "P5_7/AN119_147") (pintype "bidirectional"))
    )
    (net (code "85") (name "P5_11") (class "Default")
      (node (ref "U5") (pin "176") (pinfunction "P5_11_176") (pintype "bidirectional"))
    )
    (net (code "86") (name "P5_13") (class "Default")
      (node (ref "U5") (pin "174") (pinfunction "P5_13_174") (pintype "bidirectional"))
    )
    (net (code "87") (name "P6_00") (class "Default")
      (node (ref "U5") (pin "122") (pinfunction "P6_0_122") (pintype "bidirectional"))
    )
    (net (code "88") (name "P6_02") (class "Default")
      (node (ref "U5") (pin "120") (pinfunction "P6_2_120") (pintype "bidirectional"))
    )
    (net (code "89") (name "P6_03") (class "Default")
      (node (ref "U5") (pin "119") (pinfunction "P6_3_119") (pintype "bidirectional"))
    )
    (net (code "90") (name "P6_05") (class "Default")
      (node (ref "U5") (pin "117") (pinfunction "P6_5_117") (pintype "bidirectional"))
    )
    (net (code "91") (name "P6_06") (class "Default")
      (node (ref "U5") (pin "116") (pinfunction "P6_6_116") (pintype "bidirectional"))
    )
    (net (code "92") (name "P6_08") (class "Default")
      (node (ref "U5") (pin "99") (pinfunction "P6_8_99") (pintype "bidirectional"))
    )
    (net (code "93") (name "P6_09") (class "Default")
      (node (ref "U5") (pin "100") (pinfunction "P6_9_100") (pintype "bidirectional"))
    )
    (net (code "94") (name "P6_11") (class "Default")
      (node (ref "U5") (pin "102") (pinfunction "P6_11_102") (pintype "bidirectional"))
    )
    (net (code "95") (name "P6_12") (class "Default")
      (node (ref "U5") (pin "103") (pinfunction "P6_12_103") (pintype "bidirectional"))
    )
    (net (code "96") (name "P6_13") (class "Default")
      (node (ref "U5") (pin "104") (pinfunction "P6_13_104") (pintype "bidirectional"))
    )
    (net (code "97") (name "P6_14") (class "Default")
      (node (ref "U5") (pin "105") (pinfunction "P6_14_105") (pintype "bidirectional"))
    )
    (net (code "98") (name "P6_15") (class "Default")
      (node (ref "U5") (pin "106") (pinfunction "P6_15_106") (pintype "bidirectional"))
    )
    (net (code "99") (name "P006_AN102") (class "Default")
      (node (ref "U5") (pin "163") (pinfunction "P0_6/AN102_163") (pintype "bidirectional"))
    )
    (net (code "100") (name "P007") (class "Default")
      (node (ref "U5") (pin "162") (pinfunction "P0_7/PGVSS100_162") (pintype "bidirectional"))
    )
    (net (code "101") (name "P8_00") (class "Default")
      (node (ref "U5") (pin "133") (pinfunction "P8_0_133") (pintype "bidirectional"))
    )
    (net (code "102") (name "P8_01") (class "Default")
      (node (ref "U5") (pin "134") (pinfunction "P8_1_134") (pintype "bidirectional"))
    )
    (net (code "103") (name "P8_02") (class "Default")
      (node (ref "U5") (pin "135") (pinfunction "P8_2_135") (pintype "bidirectional"))
    )
    (net (code "104") (name "P8_03") (class "Default")
      (node (ref "U5") (pin "136") (pinfunction "P8_3_136") (pintype "bidirectional"))
    )
    (net (code "105") (name "P8_04") (class "Default")
      (node (ref "U5") (pin "137") (pinfunction "P8_4_137") (pintype "bidirectional"))
    )
    (net (code "106") (name "P8_05") (class "Default")
      (node (ref "U5") (pin "173") (pinfunction "P8_5_173") (pintype "bidirectional"))
    )
    (net (code "107") (name "P008_AN003") (class "Default")
      (node (ref "U5") (pin "161") (pinfunction "P0_8/AN003_161") (pintype "bidirectional"))
    )
    (net (code "108") (name "P9_00") (class "Default")
      (node (ref "U5") (pin "58") (pinfunction "P9_0_58") (pintype "bidirectional"))
    )
    (net (code "109") (name "P9_01") (class "Default")
      (node (ref "U5") (pin "59") (pinfunction "P9_1_59") (pintype "bidirectional"))
    )
    (net (code "110") (name "P9_05") (class "Default")
      (node (ref "U5") (pin "73") (pinfunction "P9_5_73") (pintype "bidirectional"))
    )
    (net (code "111") (name "P9_06") (class "Default")
      (node (ref "U5") (pin "72") (pinfunction "P9_6_72") (pintype "bidirectional"))
    )
    (net (code "112") (name "P9_07") (class "Default")
      (node (ref "U5") (pin "71") (pinfunction "P9_7_71") (pintype "bidirectional"))
    )
    (net (code "113") (name "P9_08") (class "Default")
      (node (ref "U5") (pin "70") (pinfunction "P9_8_70") (pintype "bidirectional"))
    )
    (net (code "114") (name "P009_AN004") (class "Default")
      (node (ref "U5") (pin "160") (pinfunction "P0_9/AN004_160") (pintype "bidirectional"))
    )
    (net (code "115") (name "P014_DA0_AN005_AN105") (class "Default")
      (node (ref "U5") (pin "152") (pinfunction "P0_14/DA0/AN005/AN105_152") (pintype "bidirectional"))
    )
    (net (code "116") (name "P015_DA1_AN006_AN106") (class "Default")
      (node (ref "U5") (pin "151") (pinfunction "P0_15/DA1/AN006/AN106_151") (pintype "bidirectional"))
    )
    (net (code "117") (name "P400_ADC") (class "Default")
      (node (ref "U5") (pin "1") (pinfunction "P4_0_1") (pintype "bidirectional"))
    )
    (net (code "118") (name "PA_00") (class "Default")
      (node (ref "U5") (pin "114") (pinfunction "PA_0_114") (pintype "bidirectional"))
    )
    (net (code "119") (name "PA_01") (class "Default")
      (node (ref "U5") (pin "113") (pinfunction "PA_1_113") (pintype "bidirectional"))
    )
    (net (code "120") (name "PA_08") (class "Default")
      (node (ref "U5") (pin "107") (pinfunction "PA_8_107") (pintype "bidirectional"))
    )
    (net (code "121") (name "PA_09") (class "Default")
      (node (ref "U5") (pin "108") (pinfunction "PA_9_108") (pintype "bidirectional"))
    )
    (net (code "122") (name "PA_10") (class "Default")
      (node (ref "U5") (pin "109") (pinfunction "PA_10_109") (pintype "bidirectional"))
    )
    (net (code "123") (name "RELAY_1") (class "Default")
      (node (ref "J4") (pin "P$15") (pinfunction "P$15_P$15") (pintype "bidirectional"))
      (node (ref "U5") (pin "68") (pinfunction "P2_1/MD_68") (pintype "bidirectional"))
    )
    (net (code "124") (name "RELAY_2") (class "Default")
      (node (ref "J4") (pin "P$17") (pinfunction "P$17_P$17") (pintype "bidirectional"))
      (node (ref "U5") (pin "54") (pinfunction "P2_2_54") (pintype "bidirectional"))
    )
    (net (code "125") (name "RELAY_3") (class "Default")
      (node (ref "J4") (pin "P$19") (pinfunction "P$19_P$19") (pintype "bidirectional"))
      (node (ref "U5") (pin "53") (pinfunction "P2_3_53") (pintype "bidirectional"))
    )
    (net (code "126") (name "RELAY_4") (class "Default")
      (node (ref "J4") (pin "P$20") (pinfunction "P$20_P$20") (pintype "bidirectional"))
      (node (ref "U5") (pin "52") (pinfunction "P2_4_52") (pintype "bidirectional"))
    )
    (net (code "127") (name "RESET") (class "Default")
      (node (ref "C29") (pin "P$1") (pinfunction "1_P$1") (pintype "passive"))
      (node (ref "J1") (pin "9") (pinfunction "9_9") (pintype "passive"))
      (node (ref "R10") (pin "P$1") (pinfunction "1_P$1") (pintype "passive"))
      (node (ref "U5") (pin "67") (pinfunction "RES#_67") (pintype "bidirectional"))
    )
    (net (code "128") (name "TCK") (class "Default")
      (node (ref "J1") (pin "7") (pinfunction "7_7") (pintype "passive"))
      (node (ref "U5") (pin "88") (pinfunction "P3_0_88") (pintype "bidirectional"))
    )
    (net (code "129") (name "TDI") (class "Default")
      (node (ref "J1") (pin "1") (pinfunction "1_1") (pintype "passive"))
      (node (ref "U5") (pin "91") (pinfunction "P1_10_91") (pintype "bidirectional"))
    )
    (net (code "130") (name "TDO") (class "Default")
      (node (ref "J1") (pin "3") (pinfunction "3_3") (pintype "passive"))
      (node (ref "U5") (pin "90") (pinfunction "P1_9_90") (pintype "bidirectional"))
    )
    (net (code "131") (name "TMS") (class "Default")
      (node (ref "J1") (pin "5") (pinfunction "5_5") (pintype "passive"))
      (node (ref "U5") (pin "89") (pinfunction "P1_8_89") (pintype "bidirectional"))
    )
    (net (code "132") (name "USBHS_FAULT") (class "Default")
      (node (ref "R2") (pin "P$1") (pinfunction "1_P$1") (pintype "passive"))
      (node (ref "U2") (pin "3") (pinfunction "FLG_3") (pintype "input"))
      (node (ref "U5") (pin "78") (pinfunction "P3_8_78") (pintype "bidirectional"))
    )
    (net (code "133") (name "USBHS_N") (class "Default")
      (node (ref "U5") (pin "31") (pinfunction "USBHS_DM_31") (pintype "bidirectional"))
      (node (ref "USB1") (pin "D-") (pinfunction "D-_D-") (pintype "bidirectional"))
    )
    (net (code "134") (name "USBHS_P") (class "Default")
      (node (ref "U5") (pin "32") (pinfunction "USBHS_DP_32") (pintype "bidirectional"))
      (node (ref "USB1") (pin "D+") (pinfunction "D+_D+") (pintype "bidirectional"))
    )
    (net (code "135") (name "USBHS_VBUS") (class "Default")
      (node (ref "C15") (pin "P$1") (pinfunction "1_P$1") (pintype "passive"))
      (node (ref "C18") (pin "1") (pinfunction "1_1") (pintype "passive"))
      (node (ref "U2") (pin "5") (pinfunction "OUT_5") (pintype "input"))
      (node (ref "U5") (pin "17") (pinfunction "PB_1_17") (pintype "bidirectional"))
      (node (ref "USB1") (pin "VBUS") (pinfunction "VBUS_VBUS") (pintype "power_in"))
    )
    (net (code "136") (name "USBHS_VBUSEN") (class "Default")
      (node (ref "R3") (pin "P$1") (pinfunction "1_P$1") (pintype "passive"))
      (node (ref "U2") (pin "1") (pinfunction "EN_1") (pintype "input"))
    )
    (net (code "137") (name "USB_N") (class "Default")
      (node (ref "R5") (pin "P$1") (pinfunction "1_P$1") (pintype "passive"))
      (node (ref "U5") (pin "46") (pinfunction "USB_DM_46") (pintype "bidirectional"))
    )
    (net (code "138") (name "USB_P") (class "Default")
      (node (ref "R6") (pin "P$1") (pinfunction "1_P$1") (pintype "passive"))
      (node (ref "U5") (pin "47") (pinfunction "USB_DP_47") (pintype "bidirectional"))
    )
    (net (code "139") (name "USB_VBUS_B") (class "Default")
      (node (ref "R4") (pin "P$1") (pinfunction "1_P$1") (pintype "passive"))
      (node (ref "U5") (pin "44") (pinfunction "P4_7_44") (pintype "bidirectional"))
    )
    (net (code "140") (name "VCL_F(FLASH)") (class "Default")
      (node (ref "C21") (pin "P$2") (pinfunction "2_P$2") (pintype "passive"))
      (node (ref "U5") (pin "112") (pinfunction "VCL_F(FLASH)_112") (pintype "bidirectional"))
    )
    (net (code "141") (name "VDD") (class "Default")
      (node (ref "C10") (pin "P$2") (pinfunction "2_P$2") (pintype "passive"))
      (node (ref "C12") (pin "P$2") (pinfunction "2_P$2") (pintype "passive"))
      (node (ref "C13") (pin "P$2") (pinfunction "2_P$2") (pintype "passive"))
      (node (ref "C17") (pin "P$2") (pinfunction "2_P$2") (pintype "passive"))
      (node (ref "C2") (pin "P$1") (pinfunction "1_P$1") (pintype "passive"))
      (node (ref "C22") (pin "P$2") (pinfunction "2_P$2") (pintype "passive"))
      (node (ref "C23") (pin "P$1") (pinfunction "1_P$1") (pintype "passive"))
      (node (ref "C25") (pin "P$2") (pinfunction "2_P$2") (pintype "passive"))
      (node (ref "C26") (pin "P$1") (pinfunction "1_P$1") (pintype "passive"))
      (node (ref "C27") (pin "P$1") (pinfunction "1_P$1") (pintype "passive"))
      (node (ref "C3") (pin "P$1") (pinfunction "1_P$1") (pintype "passive"))
      (node (ref "C30") (pin "P$1") (pinfunction "1_P$1") (pintype "passive"))
      (node (ref "C31") (pin "P$2") (pinfunction "2_P$2") (pintype "passive"))
      (node (ref "C4") (pin "P$1") (pinfunction "1_P$1") (pintype "passive"))
      (node (ref "C6") (pin "P$2") (pinfunction "2_P$2") (pintype "passive"))
      (node (ref "J1") (pin "2") (pinfunction "2_2") (pintype "passive"))
      (node (ref "J1") (pin "4") (pinfunction "4_4") (pintype "passive"))
      (node (ref "J2") (pin "P$1") (pinfunction "3.3V_P$1") (pintype "power_in"))
      (node (ref "J2") (pin "P$17") (pinfunction "3.3V_P$17") (pintype "power_in"))
      (node (ref "L1") (pin "2") (pinfunction "P$2_2") (pintype "bidirectional"))
      (node (ref "R1") (pin "P$2") (pinfunction "2_P$2") (pintype "passive"))
      (node (ref "R10") (pin "P$2") (pinfunction "2_P$2") (pintype "passive"))
      (node (ref "R12") (pin "P$1") (pinfunction "1_P$1") (pintype "passive"))
      (node (ref "R13") (pin "P$1") (pinfunction "1_P$1") (pintype "passive"))
      (node (ref "U5") (pin "110") (pinfunction "VCC(IO)5_110") (pintype "bidirectional"))
      (node (ref "U5") (pin "123") (pinfunction "VCC(IO)6_123") (pintype "bidirectional"))
      (node (ref "U5") (pin "138") (pinfunction "VCC(IO)7_138") (pintype "bidirectional"))
      (node (ref "U5") (pin "149") (pinfunction "VCC(IO)8_149") (pintype "bidirectional"))
      (node (ref "U5") (pin "155") (pinfunction "AVCC0_155") (pintype "bidirectional"))
      (node (ref "U5") (pin "171") (pinfunction "VCC(IO)9_171") (pintype "bidirectional"))
      (node (ref "U5") (pin "25") (pinfunction "VCC1_25") (pintype "bidirectional"))
      (node (ref "U5") (pin "26") (pinfunction "AVCC_SUBHS_26") (pintype "bidirectional"))
      (node (ref "U5") (pin "34") (pinfunction "VCC_USBHS_34") (pintype "bidirectional"))
      (node (ref "U5") (pin "48") (pinfunction "VCC_USB_48") (pintype "bidirectional"))
      (node (ref "U5") (pin "61") (pinfunction "VCC(IO)2_61") (pintype "bidirectional"))
      (node (ref "U5") (pin "84") (pinfunction "VCC(IO)3_84") (pintype "bidirectional"))
      (node (ref "U5") (pin "97") (pinfunction "VCC(IO)4_97") (pintype "bidirectional"))
    )
    (net (code "142") (name "VDD5") (class "Default")
      (node (ref "C11") (pin "P$1") (pinfunction "1_P$1") (pintype "passive"))
      (node (ref "C8") (pin "P$1") (pinfunction "1_P$1") (pintype "passive"))
      (node (ref "J2") (pin "P$2") (pinfunction "5V_P$2") (pintype "power_in"))
      (node (ref "J2") (pin "P$4") (pinfunction "5V_P$4") (pintype "power_in"))
      (node (ref "J3") (pin "P$3") (pinfunction "P$3_P$3") (pintype "bidirectional"))
      (node (ref "R2") (pin "P$2") (pinfunction "2_P$2") (pintype "passive"))
      (node (ref "R3") (pin "P$2") (pinfunction "2_P$2") (pintype "passive"))
      (node (ref "U2") (pin "4") (pinfunction "VIN_4") (pintype "input"))
    )
    (net (code "143") (name "VDDIN") (class "Default")
      (node (ref "J3") (pin "P$2") (pinfunction "P$2_P$2") (pintype "bidirectional"))
      (node (ref "L1") (pin "1") (pinfunction "P$1_1") (pintype "bidirectional"))
    )
    (net (code "144") (name "XCIN") (class "Default")
      (node (ref "C19") (pin "P$1") (pinfunction "1_P$1") (pintype "passive"))
      (node (ref "U5") (pin "20") (pinfunction "XCIN_20") (pintype "bidirectional"))
      (node (ref "X2") (pin "P$1") (pinfunction "P$1_P$1") (pintype "bidirectional"))
    )
    (net (code "145") (name "XCOUT") (class "Default")
      (node (ref "C24") (pin "P$1") (pinfunction "1_P$1") (pintype "passive"))
      (node (ref "U5") (pin "21") (pinfunction "XCOUT_21") (pintype "bidirectional"))
      (node (ref "X2") (pin "P$2") (pinfunction "P$2_P$2") (pintype "bidirectional"))
    )
    (net (code "146") (name "XTAL1") (class "Default")
      (node (ref "C7") (pin "P$1") (pinfunction "1_P$1") (pintype "passive"))
      (node (ref "U5") (pin "23") (pinfunction "P2_13/XTAL_23") (pintype "bidirectional"))
      (node (ref "X1") (pin "1") (pinfunction "1_1") (pintype "bidirectional"))
    )
    (net (code "147") (name "XTAL2") (class "Default")
      (node (ref "C14") (pin "P$1") (pinfunction "1_P$1") (pintype "passive"))
      (node (ref "U5") (pin "24") (pinfunction "P2_12/EXTAL_24") (pintype "bidirectional"))
      (node (ref "X1") (pin "3") (pinfunction "3_3") (pintype "bidirectional"))
    )
    (net (code "148") (name "X_DIR") (class "Default")
      (node (ref "J4") (pin "P$3") (pinfunction "P$3_P$3") (pintype "bidirectional"))
      (node (ref "U5") (pin "118") (pinfunction "P6_4_118") (pintype "bidirectional"))
    )
    (net (code "149") (name "X_LS") (class "Default")
      (node (ref "J4") (pin "P$2") (pinfunction "P$2_P$2") (pintype "bidirectional"))
      (node (ref "U5") (pin "164") (pinfunction "P0_5/AN101_164") (pintype "bidirectional"))
    )
    (net (code "150") (name "X_STEP") (class "Default")
      (node (ref "J4") (pin "P$11") (pinfunction "P$11_P$11") (pintype "bidirectional"))
      (node (ref "U5") (pin "86") (pinfunction "P3_2_86") (pintype "bidirectional"))
    )
    (net (code "151") (name "Y_DIR") (class "Default")
      (node (ref "J4") (pin "P$5") (pinfunction "P$5_P$5") (pintype "bidirectional"))
      (node (ref "U5") (pin "115") (pinfunction "P6_7_115") (pintype "bidirectional"))
    )
    (net (code "152") (name "Y_LS") (class "Default")
      (node (ref "J4") (pin "P$4") (pinfunction "P$4_P$4") (pintype "bidirectional"))
      (node (ref "U5") (pin "175") (pinfunction "P5_12_175") (pintype "bidirectional"))
    )
    (net (code "153") (name "Y_STEP") (class "Default")
      (node (ref "J4") (pin "P$13") (pinfunction "P$13_P$13") (pintype "bidirectional"))
      (node (ref "U5") (pin "82") (pinfunction "P3_4_82") (pintype "bidirectional"))
    )
    (net (code "154") (name "Z_DIR") (class "Default")
      (node (ref "J4") (pin "P$1") (pinfunction "P$1_P$1") (pintype "bidirectional"))
      (node (ref "U5") (pin "121") (pinfunction "P6_1_121") (pintype "bidirectional"))
    )
    (net (code "155") (name "Z_LS") (class "Default")
      (node (ref "J4") (pin "P$6") (pinfunction "P$6_P$6") (pintype "bidirectional"))
      (node (ref "U5") (pin "169") (pinfunction "P0_0/AN0\\00_169") (pintype "bidirectional"))
    )
    (net (code "156") (name "Z_STEP") (class "Default")
      (node (ref "J4") (pin "P$9") (pinfunction "P$9_P$9") (pintype "bidirectional"))
      (node (ref "U5") (pin "92") (pinfunction "P1_11_92") (pintype "bidirectional"))
    )
    (net (code "157") (name "unconnected-(J2-CE0-PadP$24)") (class "Default")
      (node (ref "J2") (pin "P$24") (pinfunction "CE0_P$24") (pintype "output"))
    )
    (net (code "158") (name "unconnected-(J2-CE1-PadP$26)") (class "Default")
      (node (ref "J2") (pin "P$26") (pinfunction "CE1_P$26") (pintype "output"))
    )
    (net (code "159") (name "unconnected-(J2-ID_SC-PadP$28)") (class "Default")
      (node (ref "J2") (pin "P$28") (pinfunction "ID_SC_P$28") (pintype "bidirectional"))
    )
    (net (code "160") (name "unconnected-(J2-ID_SD-PadP$27)") (class "Default")
      (node (ref "J2") (pin "P$27") (pinfunction "ID_SD_P$27") (pintype "bidirectional"))
    )
    (net (code "161") (name "unconnected-(J2-MISO-PadP$21)") (class "Default")
      (node (ref "J2") (pin "P$21") (pinfunction "MISO_P$21") (pintype "input"))
    )
    (net (code "162") (name "unconnected-(J2-MOSI-PadP$19)") (class "Default")
      (node (ref "J2") (pin "P$19") (pinfunction "MOSI_P$19") (pintype "output"))
    )
    (net (code "163") (name "unconnected-(J2-RXI-PadP$10)") (class "Default")
      (node (ref "J2") (pin "P$10") (pinfunction "RXI_P$10") (pintype "input"))
    )
    (net (code "164") (name "unconnected-(J2-SCLK-PadP$23)") (class "Default")
      (node (ref "J2") (pin "P$23") (pinfunction "SCLK_P$23") (pintype "output"))
    )
    (net (code "165") (name "unconnected-(J2-TXO-PadP$8)") (class "Default")
      (node (ref "J2") (pin "P$8") (pinfunction "TXO_P$8") (pintype "output"))
    )
    (net (code "166") (name "unconnected-(J5-PadP$1)") (class "Default")
      (node (ref "J5") (pin "P$1") (pinfunction "P$1_P$1") (pintype "bidirectional"))
    )
    (net (code "167") (name "unconnected-(J5-PadP$2)") (class "Default")
      (node (ref "J5") (pin "P$2") (pinfunction "P$2_P$2") (pintype "bidirectional"))
    )
    (net (code "168") (name "unconnected-(J5-PadP$3)") (class "Default")
      (node (ref "J5") (pin "P$3") (pinfunction "P$3_P$3") (pintype "bidirectional"))
    )
    (net (code "169") (name "unconnected-(J5-PadP$4)") (class "Default")
      (node (ref "J5") (pin "P$4") (pinfunction "P$4_P$4") (pintype "bidirectional"))
    )
    (net (code "170") (name "unconnected-(J5-PadP$5)") (class "Default")
      (node (ref "J5") (pin "P$5") (pinfunction "P$5_P$5") (pintype "bidirectional"))
    )
    (net (code "171") (name "unconnected-(J5-PadP$6)") (class "Default")
      (node (ref "J5") (pin "P$6") (pinfunction "P$6_P$6") (pintype "bidirectional"))
    )
    (net (code "172") (name "unconnected-(J5-PadP$7)") (class "Default")
      (node (ref "J5") (pin "P$7") (pinfunction "P$7_P$7") (pintype "bidirectional"))
    )
    (net (code "173") (name "unconnected-(J5-PadP$8)") (class "Default")
      (node (ref "J5") (pin "P$8") (pinfunction "P$8_P$8") (pintype "bidirectional"))
    )
    (net (code "174") (name "unconnected-(J5-PadP$9)") (class "Default")
      (node (ref "J5") (pin "P$9") (pinfunction "P$9_P$9") (pintype "bidirectional"))
    )
    (net (code "175") (name "unconnected-(J5-PadP$10)") (class "Default")
      (node (ref "J5") (pin "P$10") (pinfunction "P$10_P$10") (pintype "bidirectional"))
    )
    (net (code "176") (name "unconnected-(J5-PadP$11)") (class "Default")
      (node (ref "J5") (pin "P$11") (pinfunction "P$11_P$11") (pintype "bidirectional"))
    )
    (net (code "177") (name "unconnected-(J5-PadP$12)") (class "Default")
      (node (ref "J5") (pin "P$12") (pinfunction "P$12_P$12") (pintype "bidirectional"))
    )
    (net (code "178") (name "unconnected-(J5-PadP$13)") (class "Default")
      (node (ref "J5") (pin "P$13") (pinfunction "P$13_P$13") (pintype "bidirectional"))
    )
    (net (code "179") (name "unconnected-(J5-PadP$14)") (class "Default")
      (node (ref "J5") (pin "P$14") (pinfunction "P$14_P$14") (pintype "bidirectional"))
    )
    (net (code "180") (name "unconnected-(J5-PadP$15)") (class "Default")
      (node (ref "J5") (pin "P$15") (pinfunction "P$15_P$15") (pintype "bidirectional"))
    )
    (net (code "181") (name "unconnected-(J5-PadP$16)") (class "Default")
      (node (ref "J5") (pin "P$16") (pinfunction "P$16_P$16") (pintype "bidirectional"))
    )
    (net (code "182") (name "unconnected-(J5-PadP$17)") (class "Default")
      (node (ref "J5") (pin "P$17") (pinfunction "P$17_P$17") (pintype "bidirectional"))
    )
    (net (code "183") (name "unconnected-(J5-PadP$18)") (class "Default")
      (node (ref "J5") (pin "P$18") (pinfunction "P$18_P$18") (pintype "bidirectional"))
    )
    (net (code "184") (name "unconnected-(J5-PadP$19)") (class "Default")
      (node (ref "J5") (pin "P$19") (pinfunction "P$19_P$19") (pintype "bidirectional"))
    )
    (net (code "185") (name "unconnected-(J5-PadP$20)") (class "Default")
      (node (ref "J5") (pin "P$20") (pinfunction "P$20_P$20") (pintype "bidirectional"))
    )
    (net (code "186") (name "unconnected-(J5-PadP$21)") (class "Default")
      (node (ref "J5") (pin "P$21") (pinfunction "P$21_P$21") (pintype "bidirectional"))
    )
    (net (code "187") (name "unconnected-(J5-PadP$22)") (class "Default")
      (node (ref "J5") (pin "P$22") (pinfunction "P$22_P$22") (pintype "bidirectional"))
    )
    (net (code "188") (name "unconnected-(J5-PadP$23)") (class "Default")
      (node (ref "J5") (pin "P$23") (pinfunction "P$23_P$23") (pintype "bidirectional"))
    )
    (net (code "189") (name "unconnected-(J5-PadP$24)") (class "Default")
      (node (ref "J5") (pin "P$24") (pinfunction "P$24_P$24") (pintype "bidirectional"))
    )
    (net (code "190") (name "unconnected-(J5-PadP$25)") (class "Default")
      (node (ref "J5") (pin "P$25") (pinfunction "P$25_P$25") (pintype "bidirectional"))
    )
    (net (code "191") (name "unconnected-(J5-PadP$26)") (class "Default")
      (node (ref "J5") (pin "P$26") (pinfunction "P$26_P$26") (pintype "bidirectional"))
    )
    (net (code "192") (name "unconnected-(J5-PadP$27)") (class "Default")
      (node (ref "J5") (pin "P$27") (pinfunction "P$27_P$27") (pintype "bidirectional"))
    )
    (net (code "193") (name "unconnected-(J5-PadP$28)") (class "Default")
      (node (ref "J5") (pin "P$28") (pinfunction "P$28_P$28") (pintype "bidirectional"))
    )
    (net (code "194") (name "unconnected-(J5-PadP$29)") (class "Default")
      (node (ref "J5") (pin "P$29") (pinfunction "P$29_P$29") (pintype "bidirectional"))
    )
    (net (code "195") (name "unconnected-(J5-PadP$30)") (class "Default")
      (node (ref "J5") (pin "P$30") (pinfunction "P$30_P$30") (pintype "bidirectional"))
    )
    (net (code "196") (name "unconnected-(J5-PadP$31)") (class "Default")
      (node (ref "J5") (pin "P$31") (pinfunction "P$31_P$31") (pintype "bidirectional"))
    )
    (net (code "197") (name "unconnected-(J5-PadP$32)") (class "Default")
      (node (ref "J5") (pin "P$32") (pinfunction "P$32_P$32") (pintype "bidirectional"))
    )
    (net (code "198") (name "unconnected-(J5-PadP$33)") (class "Default")
      (node (ref "J5") (pin "P$33") (pinfunction "P$33_P$33") (pintype "bidirectional"))
    )
    (net (code "199") (name "unconnected-(J5-PadP$34)") (class "Default")
      (node (ref "J5") (pin "P$34") (pinfunction "P$34_P$34") (pintype "bidirectional"))
    )
    (net (code "200") (name "unconnected-(J5-PadP$35)") (class "Default")
      (node (ref "J5") (pin "P$35") (pinfunction "P$35_P$35") (pintype "bidirectional"))
    )
    (net (code "201") (name "unconnected-(J5-PadP$36)") (class "Default")
      (node (ref "J5") (pin "P$36") (pinfunction "P$36_P$36") (pintype "bidirectional"))
    )
    (net (code "202") (name "unconnected-(J5-PadP$37)") (class "Default")
      (node (ref "J5") (pin "P$37") (pinfunction "P$37_P$37") (pintype "bidirectional"))
    )
    (net (code "203") (name "unconnected-(J5-PadP$38)") (class "Default")
      (node (ref "J5") (pin "P$38") (pinfunction "P$38_P$38") (pintype "bidirectional"))
    )
    (net (code "204") (name "unconnected-(J5-PadP$39)") (class "Default")
      (node (ref "J5") (pin "P$39") (pinfunction "P$39_P$39") (pintype "bidirectional"))
    )
    (net (code "205") (name "unconnected-(J5-PadP$40)") (class "Default")
      (node (ref "J5") (pin "P$40") (pinfunction "P$40_P$40") (pintype "bidirectional"))
    )
    (net (code "206") (name "unconnected-(J6-PadP$1)") (class "Default")
      (node (ref "J6") (pin "P$1") (pinfunction "P$1_P$1") (pintype "bidirectional"))
    )
    (net (code "207") (name "unconnected-(J6-PadP$2)") (class "Default")
      (node (ref "J6") (pin "P$2") (pinfunction "P$2_P$2") (pintype "bidirectional"))
    )
    (net (code "208") (name "unconnected-(J6-PadP$3)") (class "Default")
      (node (ref "J6") (pin "P$3") (pinfunction "P$3_P$3") (pintype "bidirectional"))
    )
    (net (code "209") (name "unconnected-(J6-PadP$4)") (class "Default")
      (node (ref "J6") (pin "P$4") (pinfunction "P$4_P$4") (pintype "bidirectional"))
    )
    (net (code "210") (name "unconnected-(J6-PadP$5)") (class "Default")
      (node (ref "J6") (pin "P$5") (pinfunction "P$5_P$5") (pintype "bidirectional"))
    )
    (net (code "211") (name "unconnected-(J6-PadP$6)") (class "Default")
      (node (ref "J6") (pin "P$6") (pinfunction "P$6_P$6") (pintype "bidirectional"))
    )
    (net (code "212") (name "unconnected-(J6-PadP$7)") (class "Default")
      (node (ref "J6") (pin "P$7") (pinfunction "P$7_P$7") (pintype "bidirectional"))
    )
    (net (code "213") (name "unconnected-(J6-PadP$8)") (class "Default")
      (node (ref "J6") (pin "P$8") (pinfunction "P$8_P$8") (pintype "bidirectional"))
    )
    (net (code "214") (name "unconnected-(J6-PadP$9)") (class "Default")
      (node (ref "J6") (pin "P$9") (pinfunction "P$9_P$9") (pintype "bidirectional"))
    )
    (net (code "215") (name "unconnected-(J6-PadP$10)") (class "Default")
      (node (ref "J6") (pin "P$10") (pinfunction "P$10_P$10") (pintype "bidirectional"))
    )
    (net (code "216") (name "unconnected-(J6-PadP$11)") (class "Default")
      (node (ref "J6") (pin "P$11") (pinfunction "P$11_P$11") (pintype "bidirectional"))
    )
    (net (code "217") (name "unconnected-(J6-PadP$12)") (class "Default")
      (node (ref "J6") (pin "P$12") (pinfunction "P$12_P$12") (pintype "bidirectional"))
    )
    (net (code "218") (name "unconnected-(J6-PadP$13)") (class "Default")
      (node (ref "J6") (pin "P$13") (pinfunction "P$13_P$13") (pintype "bidirectional"))
    )
    (net (code "219") (name "unconnected-(J6-PadP$14)") (class "Default")
      (node (ref "J6") (pin "P$14") (pinfunction "P$14_P$14") (pintype "bidirectional"))
    )
    (net (code "220") (name "unconnected-(J6-PadP$15)") (class "Default")
      (node (ref "J6") (pin "P$15") (pinfunction "P$15_P$15") (pintype "bidirectional"))
    )
    (net (code "221") (name "unconnected-(J6-PadP$16)") (class "Default")
      (node (ref "J6") (pin "P$16") (pinfunction "P$16_P$16") (pintype "bidirectional"))
    )
    (net (code "222") (name "unconnected-(J6-PadP$17)") (class "Default")
      (node (ref "J6") (pin "P$17") (pinfunction "P$17_P$17") (pintype "bidirectional"))
    )
    (net (code "223") (name "unconnected-(J6-PadP$18)") (class "Default")
      (node (ref "J6") (pin "P$18") (pinfunction "P$18_P$18") (pintype "bidirectional"))
    )
    (net (code "224") (name "unconnected-(J6-PadP$19)") (class "Default")
      (node (ref "J6") (pin "P$19") (pinfunction "P$19_P$19") (pintype "bidirectional"))
    )
    (net (code "225") (name "unconnected-(J6-PadP$20)") (class "Default")
      (node (ref "J6") (pin "P$20") (pinfunction "P$20_P$20") (pintype "bidirectional"))
    )
    (net (code "226") (name "unconnected-(J6-PadP$21)") (class "Default")
      (node (ref "J6") (pin "P$21") (pinfunction "P$21_P$21") (pintype "bidirectional"))
    )
    (net (code "227") (name "unconnected-(J6-PadP$22)") (class "Default")
      (node (ref "J6") (pin "P$22") (pinfunction "P$22_P$22") (pintype "bidirectional"))
    )
    (net (code "228") (name "unconnected-(J6-PadP$23)") (class "Default")
      (node (ref "J6") (pin "P$23") (pinfunction "P$23_P$23") (pintype "bidirectional"))
    )
    (net (code "229") (name "unconnected-(J6-PadP$24)") (class "Default")
      (node (ref "J6") (pin "P$24") (pinfunction "P$24_P$24") (pintype "bidirectional"))
    )
    (net (code "230") (name "unconnected-(J6-PadP$25)") (class "Default")
      (node (ref "J6") (pin "P$25") (pinfunction "P$25_P$25") (pintype "bidirectional"))
    )
    (net (code "231") (name "unconnected-(J6-PadP$26)") (class "Default")
      (node (ref "J6") (pin "P$26") (pinfunction "P$26_P$26") (pintype "bidirectional"))
    )
    (net (code "232") (name "unconnected-(J6-PadP$27)") (class "Default")
      (node (ref "J6") (pin "P$27") (pinfunction "P$27_P$27") (pintype "bidirectional"))
    )
    (net (code "233") (name "unconnected-(J6-PadP$28)") (class "Default")
      (node (ref "J6") (pin "P$28") (pinfunction "P$28_P$28") (pintype "bidirectional"))
    )
    (net (code "234") (name "unconnected-(J6-PadP$29)") (class "Default")
      (node (ref "J6") (pin "P$29") (pinfunction "P$29_P$29") (pintype "bidirectional"))
    )
    (net (code "235") (name "unconnected-(J6-PadP$30)") (class "Default")
      (node (ref "J6") (pin "P$30") (pinfunction "P$30_P$30") (pintype "bidirectional"))
    )
    (net (code "236") (name "unconnected-(J6-PadP$31)") (class "Default")
      (node (ref "J6") (pin "P$31") (pinfunction "P$31_P$31") (pintype "bidirectional"))
    )
    (net (code "237") (name "unconnected-(J6-PadP$32)") (class "Default")
      (node (ref "J6") (pin "P$32") (pinfunction "P$32_P$32") (pintype "bidirectional"))
    )
    (net (code "238") (name "unconnected-(J6-PadP$33)") (class "Default")
      (node (ref "J6") (pin "P$33") (pinfunction "P$33_P$33") (pintype "bidirectional"))
    )
    (net (code "239") (name "unconnected-(J6-PadP$34)") (class "Default")
      (node (ref "J6") (pin "P$34") (pinfunction "P$34_P$34") (pintype "bidirectional"))
    )
    (net (code "240") (name "unconnected-(J6-PadP$35)") (class "Default")
      (node (ref "J6") (pin "P$35") (pinfunction "P$35_P$35") (pintype "bidirectional"))
    )
    (net (code "241") (name "unconnected-(J6-PadP$36)") (class "Default")
      (node (ref "J6") (pin "P$36") (pinfunction "P$36_P$36") (pintype "bidirectional"))
    )
    (net (code "242") (name "unconnected-(J6-PadP$37)") (class "Default")
      (node (ref "J6") (pin "P$37") (pinfunction "P$37_P$37") (pintype "bidirectional"))
    )
    (net (code "243") (name "unconnected-(J6-PadP$39)") (class "Default")
      (node (ref "J6") (pin "P$39") (pinfunction "P$39_P$39") (pintype "bidirectional"))
    )
    (net (code "244") (name "unconnected-(U5-P4_1-Pad2)") (class "Default")
      (node (ref "U5") (pin "2") (pinfunction "P4_1_2") (pintype "bidirectional"))
    )
    (net (code "245") (name "unconnected-(U5-P4_2-Pad3)") (class "Default")
      (node (ref "U5") (pin "3") (pinfunction "P4_2_3") (pintype "bidirectional"))
    )
    (net (code "246") (name "unconnected-(U5-P4_8-Pad43)") (class "Default")
      (node (ref "U5") (pin "43") (pinfunction "P4_8_43") (pintype "bidirectional"))
    )
    (net (code "247") (name "unconnected-(U5-P4_10-Pad41)") (class "Default")
      (node (ref "U5") (pin "41") (pinfunction "P4_10_41") (pintype "bidirectional"))
    )
    (net (code "248") (name "unconnected-(U5-P4_11-Pad40)") (class "Default")
      (node (ref "U5") (pin "40") (pinfunction "P4_11_40") (pintype "bidirectional"))
    )
    (net (code "249") (name "unconnected-(U5-P4_12-Pad39)") (class "Default")
      (node (ref "U5") (pin "39") (pinfunction "P4_12_39") (pintype "bidirectional"))
    )
    (net (code "250") (name "unconnected-(U5-P4_13-Pad38)") (class "Default")
      (node (ref "U5") (pin "38") (pinfunction "P4_13_38") (pintype "bidirectional"))
    )
    (net (code "251") (name "unconnected-(U5-P4_14-Pad37)") (class "Default")
      (node (ref "U5") (pin "37") (pinfunction "P4_14_37") (pintype "bidirectional"))
    )
    (net (code "252") (name "unconnected-(U5-P4_15-Pad36)") (class "Default")
      (node (ref "U5") (pin "36") (pinfunction "P4_15_36") (pintype "bidirectional"))
    )
    (net (code "253") (name "unconnected-(U5-P7_6-Pad14)") (class "Default")
      (node (ref "U5") (pin "14") (pinfunction "P7_6_14") (pintype "bidirectional"))
    )
    (net (code "254") (name "unconnected-(U5-P7_7-Pad15)") (class "Default")
      (node (ref "U5") (pin "15") (pinfunction "P7_7_15") (pintype "bidirectional"))
    )
    (net (code "255") (name "unconnected-(U5-PB_0-Pad16)") (class "Default")
      (node (ref "U5") (pin "16") (pinfunction "PB_0_16") (pintype "bidirectional"))
    )
    (net (code "256") (name "unconnected-(U5-VBAT-Pad18)") (class "Default")
      (node (ref "U5") (pin "18") (pinfunction "VBAT_18") (pintype "bidirectional"))
    )
    (net (code "257") (name "unconnected-(U5-VREFH-Pad154)") (class "Default")
      (node (ref "U5") (pin "154") (pinfunction "VREFH_154") (pintype "bidirectional"))
    )
    (net (code "258") (name "unconnected-(U5-VREFH0-Pad158)") (class "Default")
      (node (ref "U5") (pin "158") (pinfunction "VREFH0_158") (pintype "bidirectional"))
    )
    (net (code "259") (name "unconnected-(U5-VREFL-Pad153)") (class "Default")
      (node (ref "U5") (pin "153") (pinfunction "VREFL_153") (pintype "bidirectional"))
    )
    (net (code "260") (name "unconnected-(U5-VREFL0-Pad157)") (class "Default")
      (node (ref "U5") (pin "157") (pinfunction "VREFL0_157") (pintype "bidirectional"))
    )
  )
)
